# RGB_LED.net
KiCad netlist of a schematic drawn in Altium Designer
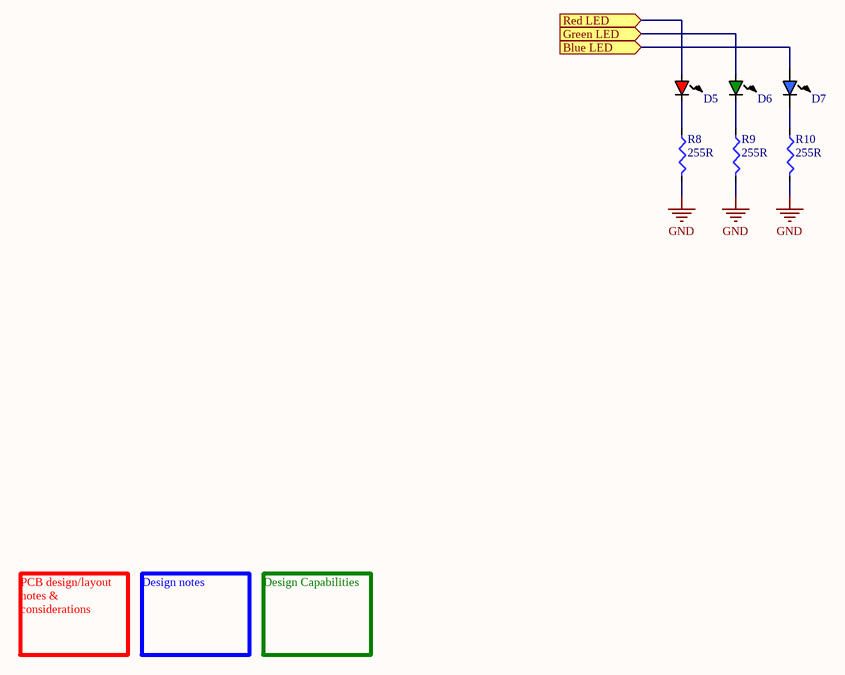
[diagram p0: RGB LED.SchDoc]

(export (version "E")
  (design (tool "Eeschema 10.0.6"))
  (components
    (comp (ref "D5")
      (value "Red LED 1206")
      (footprint "LED - 1206 Red")
      (fields
        (field (name "MANUFACTURER") "Kingbright")
        (field (name "MANUFACTURER PART NUMBER") "APT3216SRCPRV")
      )
      (libsource (lib "Personal Library") (part "Red LED 1206"))
    )
    (comp (ref "D6")
      (value "Green LED 1206")
      (footprint "LED - 1206 Green")
      (fields
        (field (name "MANUFACTURER") "Kingbright")
        (field (name "MANUFACTURER PART NUMBER") "APL3015SGC-F01")
      )
      (libsource (lib "Personal Library") (part "Green LED 1206"))
    )
    (comp (ref "D7")
      (value "Blue LED 1206")
      (footprint "LED - 1206 Blue")
      (description "Single Colour")
      (fields
        (field (name "MANUFACTURER") "Lite-On Inc")
        (field (name "MANUFACTURER PART NUMBER") "LTST-C150TBKT")
      )
      (libsource (lib "Local Library") (part "Blue LED 1206"))
    )
    (comp (ref "R8")
      (value "255R 0805 1%")
      (footprint "R0805")
      (description "1/8W")
      (fields
        (field (name "MANUFACTURER") "Panasonic Electronic Components")
        (field (name "MANUFACTURER PART NUMBER") "ERJ-6ENF2550V")
        (field (name "RESISTANCE (OHMS)") "255R")
      )
      (libsource (lib "Personal Library") (part "255R 0805 1%"))
    )
    (comp (ref "R9")
      (value "255R 0805 1%")
      (footprint "R0805")
      (description "1/8W")
      (fields
        (field (name "MANUFACTURER") "Panasonic Electronic Components")
        (field (name "MANUFACTURER PART NUMBER") "ERJ-6ENF2550V")
        (field (name "RESISTANCE (OHMS)") "255R")
      )
      (libsource (lib "Personal Library") (part "255R 0805 1%"))
    )
    (comp (ref "R10")
      (value "255R 0805 1%")
      (footprint "R0805")
      (description "1/8W")
      (fields
        (field (name "MANUFACTURER") "Panasonic Electronic Components")
        (field (name "MANUFACTURER PART NUMBER") "ERJ-6ENF2550V")
        (field (name "RESISTANCE (OHMS)") "255R")
      )
      (libsource (lib "Personal Library") (part "255R 0805 1%"))
    )
  )
  (nets
    (net (code "1") (name "/Blue LED") (class "Default")
      (node (ref "D7") (pin "1") (pinfunction "1_1") (pintype "passive"))
    )
    (net (code "2") (name "/Green LED") (class "Default")
      (node (ref "D6") (pin "1") (pinfunction "1_1") (pintype "passive"))
    )
    (net (code "3") (name "/Red LED") (class "Default")
      (node (ref "D5") (pin "1") (pinfunction "1_1") (pintype "passive"))
    )
    (net (code "4") (name "GND") (class "Default")
      (node (ref "R10") (pin "1") (pinfunction "1_1") (pintype "passive"))
      (node (ref "R8") (pin "1") (pinfunction "1_1") (pintype "passive"))
      (node (ref "R9") (pin "1") (pinfunction "1_1") (pintype "passive"))
    )
    (net (code "5") (name "Net-(D5-Pad2)") (class "Default")
      (node (ref "D5") (pin "2") (pinfunction "2_2") (pintype "passive"))
      (node (ref "R8") (pin "2") (pinfunction "2_2") (pintype "passive"))
    )
    (net (code "6") (name "Net-(D6-Pad2)") (class "Default")
      (node (ref "D6") (pin "2") (pinfunction "2_2") (pintype "passive"))
      (node (ref "R9") (pin "2") (pinfunction "2_2") (pintype "passive"))
    )
    (net (code "7") (name "Net-(D7-Pad2)") (class "Default")
      (node (ref "D7") (pin "2") (pinfunction "2_2") (pintype "passive"))
      (node (ref "R10") (pin "2") (pinfunction "2_2") (pintype "passive"))
    )
  )
)
